# 1-Schematic_esp_usb.net
KiCad netlist of a schematic drawn in EasyEDA
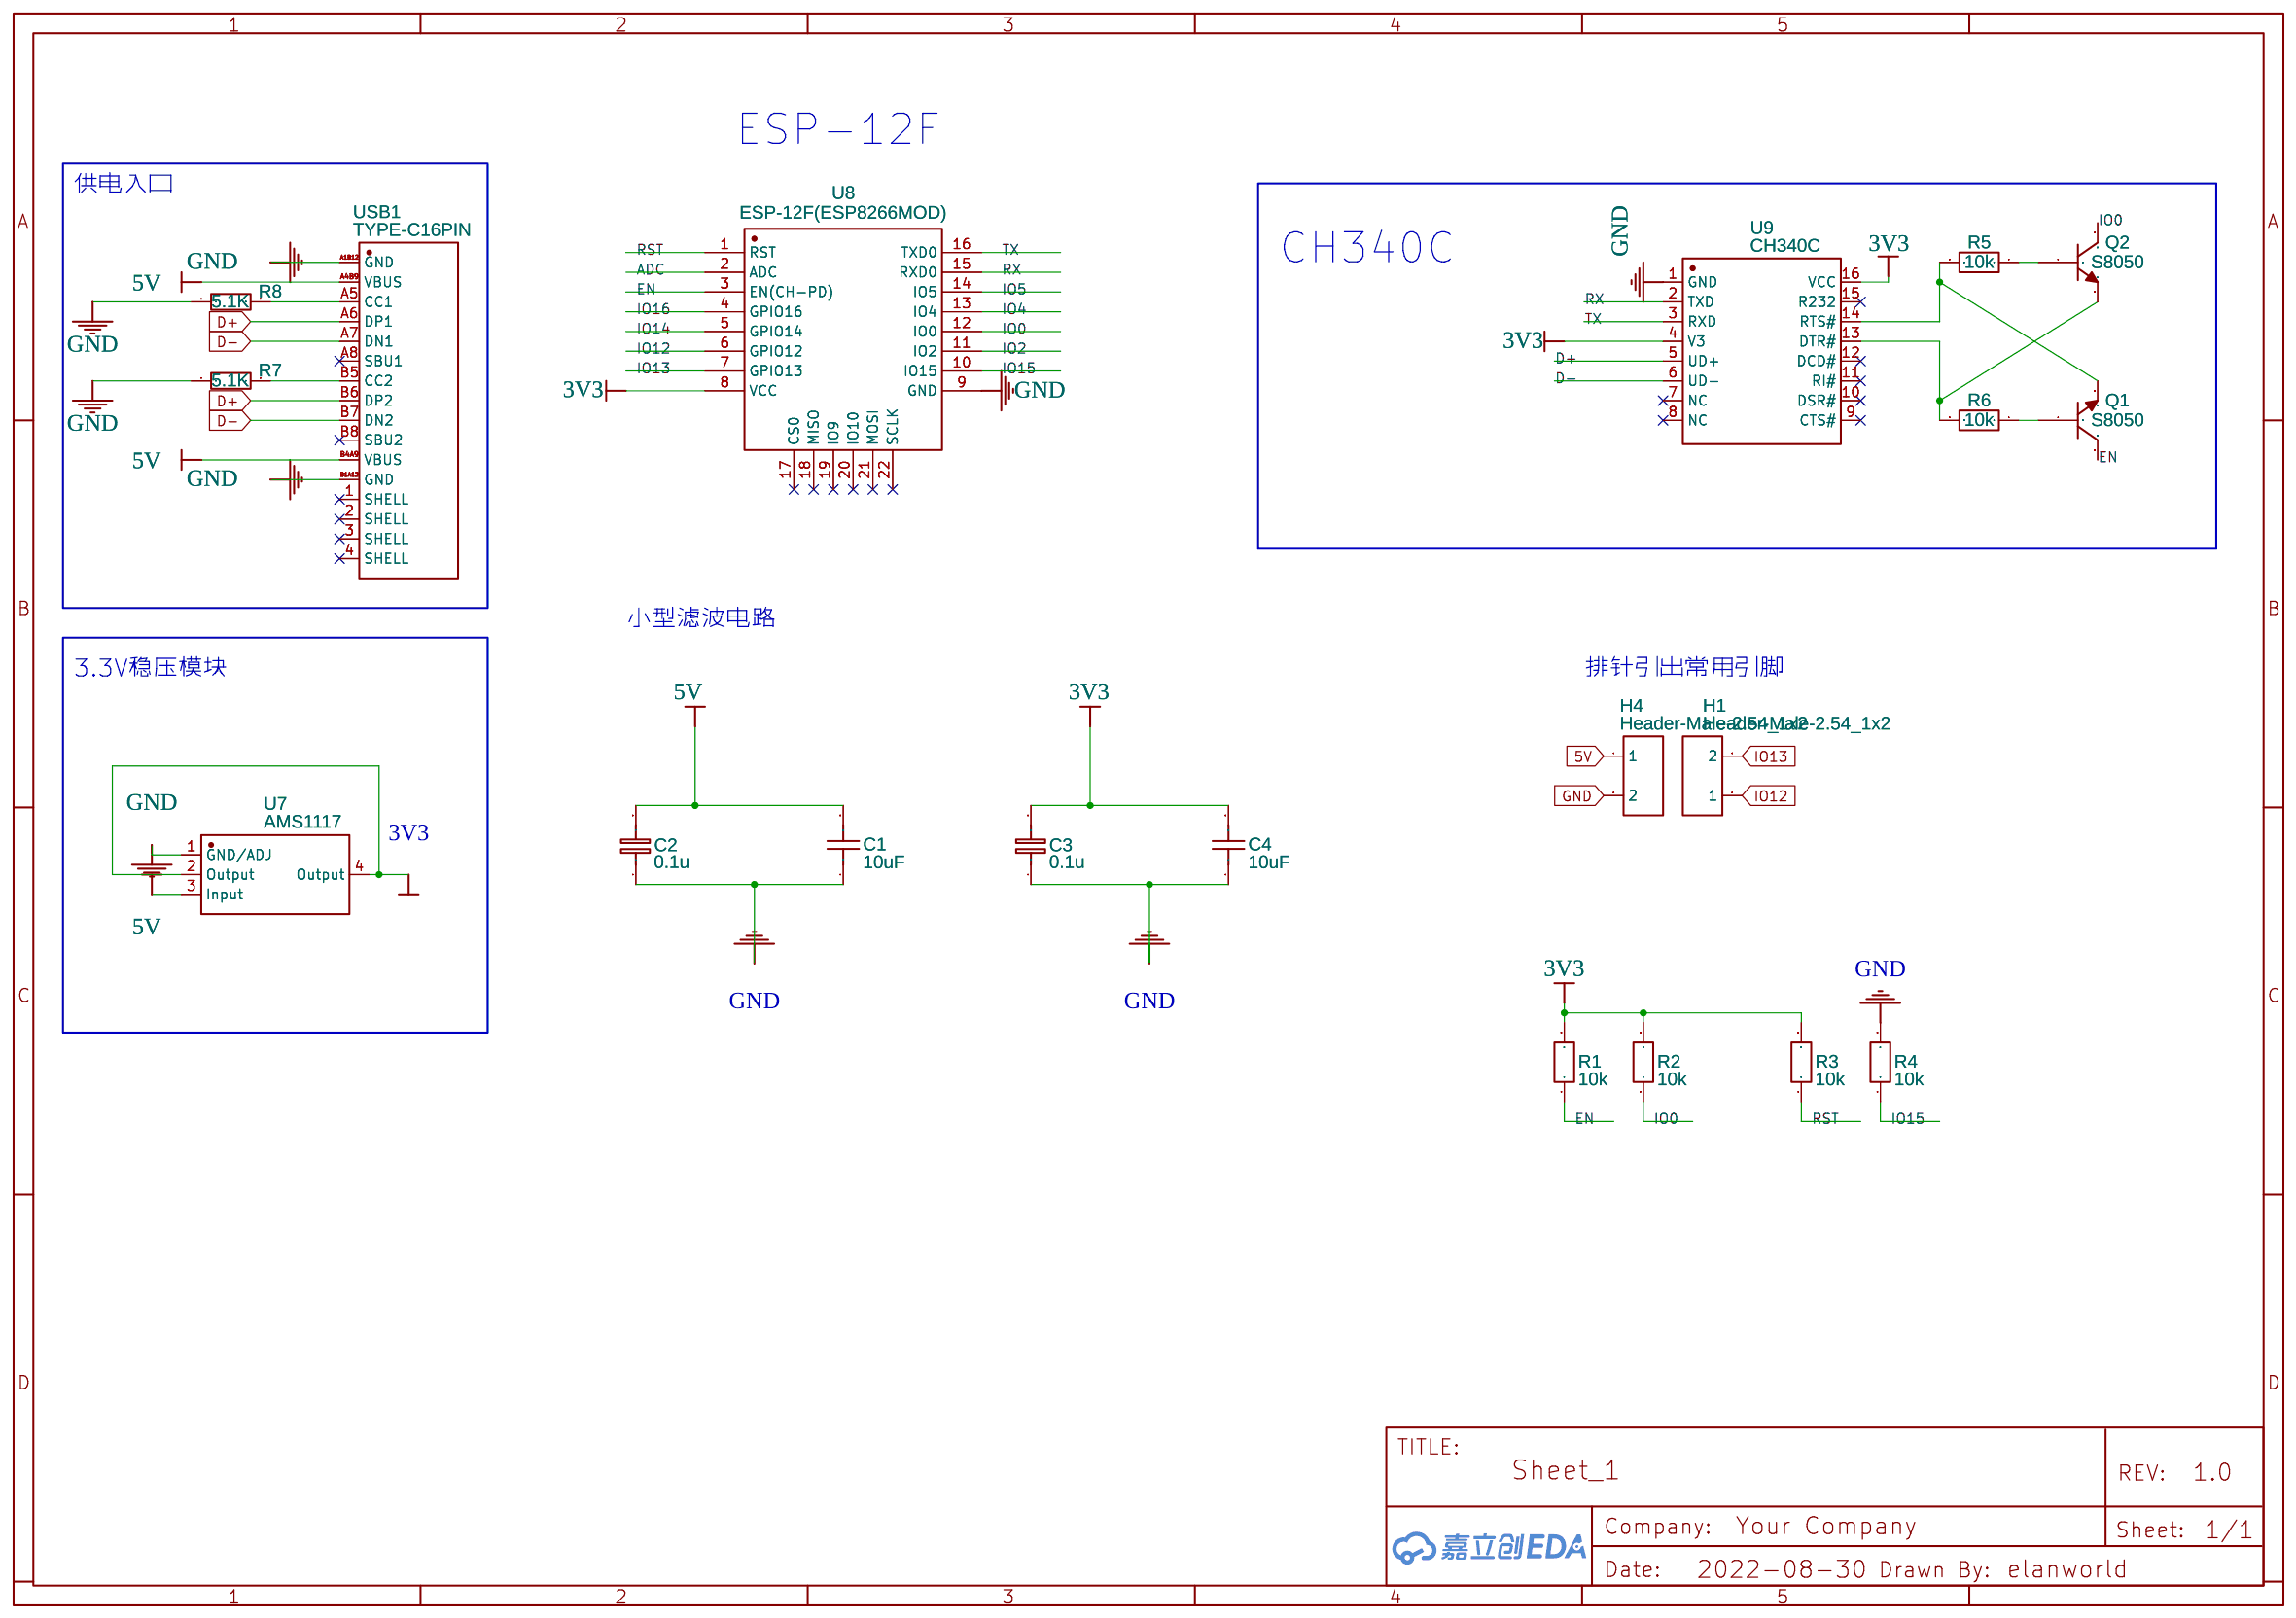
[diagram p0: schematic sheet]

(export (version "E")
  (design (tool "Eeschema 10.0.6"))
  (components
    (comp (ref "C1")
      (value "10uF")
      (fields
        (field (name "BOM_Manufacturer Part") "CL10A106MP8NNNC")
        (field (name "BOM_Supplier Part") "C85713")
      )
      (libsource (lib "") (part "CL10A106MP8NNNC"))
    )
    (comp (ref "C2")
      (value "0.1u")
      (fields (field (name "BOM_Supplier Part") "C1591"))
      (libsource (lib "") (part "C_0603_EU_1"))
    )
    (comp (ref "C3")
      (value "0.1u")
      (fields (field (name "BOM_Supplier Part") "C1591"))
      (libsource (lib "") (part "C_0603_EU"))
    )
    (comp (ref "C4")
      (value "10uF")
      (fields
        (field (name "BOM_Manufacturer Part") "CL10A106MP8NNNC")
        (field (name "BOM_Supplier Part") "C85713")
      )
      (libsource (lib "") (part "CL10A106MP8NNNC"))
    )
    (comp (ref "H1")
      (value "Header-Male-2.54_1x2")
      (fields (field (name "BOM_Manufacturer Part") "826629-2") (field (name "BOM_Supplier Part") "C86471"))
      (libsource (lib "") (part "Header-Male-2.54_1x2"))
    )
    (comp (ref "H4")
      (value "Header-Male-2.54_1x2")
      (fields (field (name "BOM_Manufacturer Part") "826629-2") (field (name "BOM_Supplier Part") "C86471"))
      (libsource (lib "") (part "Header-Male-2.54_1x2_1"))
    )
    (comp (ref "Q1")
      (value "S8050")
      (fields (field (name "BOM_Supplier Part") "C364312"))
      (libsource (lib "") (part "Unknown_1045_-600"))
    )
    (comp (ref "Q2")
      (value "S8050")
      (fields (field (name "BOM_Supplier Part") "C364312"))
      (libsource (lib "") (part "Unknown_1045_-680"))
    )
    (comp (ref "R1")
      (value "10k")
      (fields (field (name "BOM_Supplier Part") "C169103"))
      (libsource (lib "") (part "R_0603_EU"))
    )
    (comp (ref "R2")
      (value "10k")
      (fields (field (name "BOM_Supplier Part") "C169103"))
      (libsource (lib "") (part "R_0603_EU"))
    )
    (comp (ref "R3")
      (value "10k")
      (fields (field (name "BOM_Supplier Part") "C169103"))
      (libsource (lib "") (part "R_0603_EU"))
    )
    (comp (ref "R4")
      (value "10k")
      (fields (field (name "BOM_Supplier Part") "C169103"))
      (libsource (lib "") (part "R_0603_EU"))
    )
    (comp (ref "R5")
      (value "10k")
      (fields (field (name "BOM_Supplier Part") "C169103"))
      (libsource (lib "") (part "Res_0603(1/10W)_EU"))
    )
    (comp (ref "R6")
      (value "10k")
      (fields (field (name "BOM_Supplier Part") "C169103"))
      (libsource (lib "") (part "Res_0603(1/10W)_EU"))
    )
    (comp (ref "R7")
      (value "5.1K")
      (fields
        (field (name "BOM_Manufacturer Part") "RMC04025.1K1%N")
        (field (name "BOM_Supplier Part") "C325521")
      )
      (libsource (lib "") (part "RMC04025.1K1%N"))
    )
    (comp (ref "R8")
      (value "5.1K")
      (fields
        (field (name "BOM_Manufacturer Part") "RMC04025.1K1%N")
        (field (name "BOM_Supplier Part") "C325521")
      )
      (libsource (lib "") (part "RMC04025.1K1%N"))
    )
    (comp (ref "U7")
      (value "AMS1117")
      (fields
        (field (name "BOM_Manufacturer Part") "AMS1117-3.3")
        (field (name "BOM_Supplier Part") "C369933")
      )
      (libsource (lib "") (part "AMS1117-3.3_C369933"))
    )
    (comp (ref "U8")
      (value "ESP-12F(ESP8266MOD)")
      (fields (field (name "BOM_Supplier Part") "C82891"))
      (libsource (lib "") (part "ESP-12F(ESP8266MOD)"))
    )
    (comp (ref "U9")
      (value "CH340C")
      (fields (field (name "BOM_Supplier Part") "C84681"))
      (libsource (lib "") (part "Unknown_885_-680"))
    )
    (comp (ref "USB1")
      (value "TYPE-C16PIN")
      (fields (field (name "BOM_Supplier Part") "C393939"))
      (libsource (lib "") (part "TYPE-C16PIN"))
    )
  )
  (nets
    (net (code "1") (name "/ADC") (class "Default")
      (node (ref "U8") (pin "2") (pinfunction "ADC_2") (pintype "unspecified"))
    )
    (net (code "2") (name "/EN") (class "Default")
      (node (ref "Q1") (pin "3") (pinfunction "C_3") (pintype "unspecified"))
      (node (ref "R1") (pin "1") (pinfunction "1_1") (pintype "unspecified"))
      (node (ref "U8") (pin "3") (pinfunction "EN(CH-PD)_3") (pintype "unspecified"))
    )
    (net (code "3") (name "/IO0") (class "Default")
      (node (ref "Q2") (pin "3") (pinfunction "C_3") (pintype "unspecified"))
      (node (ref "R2") (pin "1") (pinfunction "1_1") (pintype "unspecified"))
      (node (ref "U8") (pin "12") (pinfunction "IO0_12") (pintype "unspecified"))
    )
    (net (code "4") (name "/IO2") (class "Default")
      (node (ref "U8") (pin "11") (pinfunction "IO2_11") (pintype "unspecified"))
    )
    (net (code "5") (name "/IO4") (class "Default")
      (node (ref "U8") (pin "13") (pinfunction "IO4_13") (pintype "unspecified"))
    )
    (net (code "6") (name "/IO5") (class "Default")
      (node (ref "U8") (pin "14") (pinfunction "IO5_14") (pintype "unspecified"))
    )
    (net (code "7") (name "/IO14") (class "Default")
      (node (ref "U8") (pin "5") (pinfunction "GPIO14_5") (pintype "unspecified"))
    )
    (net (code "8") (name "/IO15") (class "Default")
      (node (ref "R4") (pin "1") (pinfunction "1_1") (pintype "unspecified"))
      (node (ref "U8") (pin "10") (pinfunction "IO15_10") (pintype "unspecified"))
    )
    (net (code "9") (name "/IO16") (class "Default")
      (node (ref "U8") (pin "4") (pinfunction "GPIO16_4") (pintype "unspecified"))
    )
    (net (code "10") (name "/RST") (class "Default")
      (node (ref "R3") (pin "1") (pinfunction "1_1") (pintype "unspecified"))
      (node (ref "U8") (pin "1") (pinfunction "RST_1") (pintype "unspecified"))
    )
    (net (code "11") (name "/RX") (class "Default")
      (node (ref "U8") (pin "15") (pinfunction "RXD0_15") (pintype "unspecified"))
      (node (ref "U9") (pin "2") (pinfunction "TXD_2") (pintype "unspecified"))
    )
    (net (code "12") (name "/TX") (class "Default")
      (node (ref "U8") (pin "16") (pinfunction "TXD0_16") (pintype "unspecified"))
      (node (ref "U9") (pin "3") (pinfunction "RXD_3") (pintype "unspecified"))
    )
    (net (code "13") (name "3V3") (class "Default")
      (node (ref "C3") (pin "2") (pinfunction "2_2") (pintype "unspecified"))
      (node (ref "C4") (pin "2") (pinfunction "2_2") (pintype "unspecified"))
      (node (ref "R1") (pin "2") (pinfunction "2_2") (pintype "unspecified"))
      (node (ref "R2") (pin "2") (pinfunction "2_2") (pintype "unspecified"))
      (node (ref "R3") (pin "2") (pinfunction "2_2") (pintype "unspecified"))
      (node (ref "U7") (pin "2") (pinfunction "Output_2") (pintype "unspecified"))
      (node (ref "U7") (pin "4") (pinfunction "Output_4") (pintype "unspecified"))
      (node (ref "U8") (pin "8") (pinfunction "VCC_8") (pintype "unspecified"))
      (node (ref "U9") (pin "16") (pinfunction "VCC_16") (pintype "unspecified"))
      (node (ref "U9") (pin "4") (pinfunction "V3_4") (pintype "unspecified"))
    )
    (net (code "14") (name "5V") (class "Default")
      (node (ref "C1") (pin "2") (pinfunction "2_2") (pintype "unspecified"))
      (node (ref "C2") (pin "2") (pinfunction "2_2") (pintype "unspecified"))
      (node (ref "H4") (pin "1") (pinfunction "1_1") (pintype "unspecified"))
      (node (ref "U7") (pin "3") (pinfunction "Input_3") (pintype "unspecified"))
      (node (ref "USB1") (pin "A4B9") (pinfunction "VBUS_A4B9") (pintype "unspecified"))
      (node (ref "USB1") (pin "B4A9") (pinfunction "VBUS_B4A9") (pintype "unspecified"))
    )
    (net (code "15") (name "D+") (class "Default")
      (node (ref "U9") (pin "5") (pinfunction "UD+_5") (pintype "unspecified"))
      (node (ref "USB1") (pin "A6") (pinfunction "DP1_A6") (pintype "unspecified"))
      (node (ref "USB1") (pin "B6") (pinfunction "DP2_B6") (pintype "unspecified"))
    )
    (net (code "16") (name "D-") (class "Default")
      (node (ref "U9") (pin "6") (pinfunction "UD-_6") (pintype "unspecified"))
      (node (ref "USB1") (pin "A7") (pinfunction "DN1_A7") (pintype "unspecified"))
      (node (ref "USB1") (pin "B7") (pinfunction "DN2_B7") (pintype "unspecified"))
    )
    (net (code "17") (name "GND") (class "Default")
      (node (ref "C1") (pin "1") (pinfunction "1_1") (pintype "unspecified"))
      (node (ref "C2") (pin "1") (pinfunction "1_1") (pintype "unspecified"))
      (node (ref "C3") (pin "1") (pinfunction "1_1") (pintype "unspecified"))
      (node (ref "C4") (pin "1") (pinfunction "1_1") (pintype "unspecified"))
      (node (ref "H4") (pin "2") (pinfunction "2_2") (pintype "unspecified"))
      (node (ref "R4") (pin "2") (pinfunction "2_2") (pintype "unspecified"))
      (node (ref "R7") (pin "1") (pinfunction "1_1") (pintype "unspecified"))
      (node (ref "R8") (pin "1") (pinfunction "1_1") (pintype "unspecified"))
      (node (ref "U7") (pin "1") (pinfunction "GND/ADJ_1") (pintype "unspecified"))
      (node (ref "U8") (pin "9") (pinfunction "GND_9") (pintype "unspecified"))
      (node (ref "U9") (pin "1") (pinfunction "GND_1") (pintype "unspecified"))
      (node (ref "USB1") (pin "A1B12") (pinfunction "GND_A1B12") (pintype "unspecified"))
      (node (ref "USB1") (pin "B1A12") (pinfunction "GND_B1A12") (pintype "unspecified"))
    )
    (net (code "18") (name "IO12") (class "Default")
      (node (ref "H1") (pin "1") (pinfunction "1_1") (pintype "unspecified"))
      (node (ref "U8") (pin "6") (pinfunction "GPIO12_6") (pintype "unspecified"))
    )
    (net (code "19") (name "IO13") (class "Default")
      (node (ref "H1") (pin "2") (pinfunction "2_2") (pintype "unspecified"))
      (node (ref "U8") (pin "7") (pinfunction "GPIO13_7") (pintype "unspecified"))
    )
    (net (code "20") (name "Net-(Q1-B)") (class "Default")
      (node (ref "Q1") (pin "1") (pinfunction "B_1") (pintype "unspecified"))
      (node (ref "R6") (pin "1") (pinfunction "1_1") (pintype "unspecified"))
    )
    (net (code "21") (name "Net-(Q1-E)") (class "Default")
      (node (ref "Q1") (pin "2") (pinfunction "E_2") (pintype "unspecified"))
      (node (ref "R5") (pin "2") (pinfunction "2_2") (pintype "unspecified"))
      (node (ref "U9") (pin "14") (pinfunction "RTS#_14") (pintype "unspecified"))
    )
    (net (code "22") (name "Net-(Q2-B)") (class "Default")
      (node (ref "Q2") (pin "1") (pinfunction "B_1") (pintype "unspecified"))
      (node (ref "R5") (pin "1") (pinfunction "1_1") (pintype "unspecified"))
    )
    (net (code "23") (name "Net-(Q2-E)") (class "Default")
      (node (ref "Q2") (pin "2") (pinfunction "E_2") (pintype "unspecified"))
      (node (ref "R6") (pin "2") (pinfunction "2_2") (pintype "unspecified"))
      (node (ref "U9") (pin "13") (pinfunction "DTR#_13") (pintype "unspecified"))
    )
    (net (code "24") (name "Net-(USB1-CC1)") (class "Default")
      (node (ref "R8") (pin "2") (pinfunction "2_2") (pintype "unspecified"))
      (node (ref "USB1") (pin "A5") (pinfunction "CC1_A5") (pintype "unspecified"))
    )
    (net (code "25") (name "Net-(USB1-CC2)") (class "Default")
      (node (ref "R7") (pin "2") (pinfunction "2_2") (pintype "unspecified"))
      (node (ref "USB1") (pin "B5") (pinfunction "CC2_B5") (pintype "unspecified"))
    )
    (net (code "26") (name "unconnected-(U8-CS0-Pad17)") (class "Default")
      (node (ref "U8") (pin "17") (pinfunction "CS0_17") (pintype "unspecified+no_connect"))
    )
    (net (code "27") (name "unconnected-(U8-IO9-Pad19)") (class "Default")
      (node (ref "U8") (pin "19") (pinfunction "IO9_19") (pintype "unspecified+no_connect"))
    )
    (net (code "28") (name "unconnected-(U8-IO10-Pad20)") (class "Default")
      (node (ref "U8") (pin "20") (pinfunction "IO10_20") (pintype "unspecified+no_connect"))
    )
    (net (code "29") (name "unconnected-(U8-MISO-Pad18)") (class "Default")
      (node (ref "U8") (pin "18") (pinfunction "MISO_18") (pintype "unspecified+no_connect"))
    )
    (net (code "30") (name "unconnected-(U8-MOSI-Pad21)") (class "Default")
      (node (ref "U8") (pin "21") (pinfunction "MOSI_21") (pintype "unspecified+no_connect"))
    )
    (net (code "31") (name "unconnected-(U8-SCLK-Pad22)") (class "Default")
      (node (ref "U8") (pin "22") (pinfunction "SCLK_22") (pintype "unspecified+no_connect"))
    )
    (net (code "32") (name "unconnected-(U9-CTS#-Pad9)") (class "Default")
      (node (ref "U9") (pin "9") (pinfunction "CTS#_9") (pintype "unspecified+no_connect"))
    )
    (net (code "33") (name "unconnected-(U9-DCD#-Pad12)") (class "Default")
      (node (ref "U9") (pin "12") (pinfunction "DCD#_12") (pintype "unspecified+no_connect"))
    )
    (net (code "34") (name "unconnected-(U9-DSR#-Pad10)") (class "Default")
      (node (ref "U9") (pin "10") (pinfunction "DSR#_10") (pintype "unspecified+no_connect"))
    )
    (net (code "35") (name "unconnected-(U9-NC-Pad7)") (class "Default")
      (node (ref "U9") (pin "7") (pinfunction "NC_7") (pintype "unspecified+no_connect"))
    )
    (net (code "36") (name "unconnected-(U9-NC-Pad8)") (class "Default")
      (node (ref "U9") (pin "8") (pinfunction "NC_8") (pintype "unspecified+no_connect"))
    )
    (net (code "37") (name "unconnected-(U9-R232-Pad15)") (class "Default")
      (node (ref "U9") (pin "15") (pinfunction "R232_15") (pintype "unspecified+no_connect"))
    )
    (net (code "38") (name "unconnected-(U9-RI#-Pad11)") (class "Default")
      (node (ref "U9") (pin "11") (pinfunction "RI#_11") (pintype "unspecified+no_connect"))
    )
    (net (code "39") (name "unconnected-(USB1-SBU1-PadA8)") (class "Default")
      (node (ref "USB1") (pin "A8") (pinfunction "SBU1_A8") (pintype "unspecified+no_connect"))
    )
    (net (code "40") (name "unconnected-(USB1-SBU2-PadB8)") (class "Default")
      (node (ref "USB1") (pin "B8") (pinfunction "SBU2_B8") (pintype "unspecified+no_connect"))
    )
    (net (code "41") (name "unconnected-(USB1-SHELL-Pad1)") (class "Default")
      (node (ref "USB1") (pin "1") (pinfunction "SHELL_1") (pintype "unspecified+no_connect"))
    )
    (net (code "42") (name "unconnected-(USB1-SHELL-Pad2)") (class "Default")
      (node (ref "USB1") (pin "2") (pinfunction "SHELL_2") (pintype "unspecified+no_connect"))
    )
    (net (code "43") (name "unconnected-(USB1-SHELL-Pad3)") (class "Default")
      (node (ref "USB1") (pin "3") (pinfunction "SHELL_3") (pintype "unspecified+no_connect"))
    )
    (net (code "44") (name "unconnected-(USB1-SHELL-Pad4)") (class "Default")
      (node (ref "USB1") (pin "4") (pinfunction "SHELL_4") (pintype "unspecified+no_connect"))
    )
  )
)
